# relais_node_01.net
KiCad netlist of a schematic drawn in EAGLE
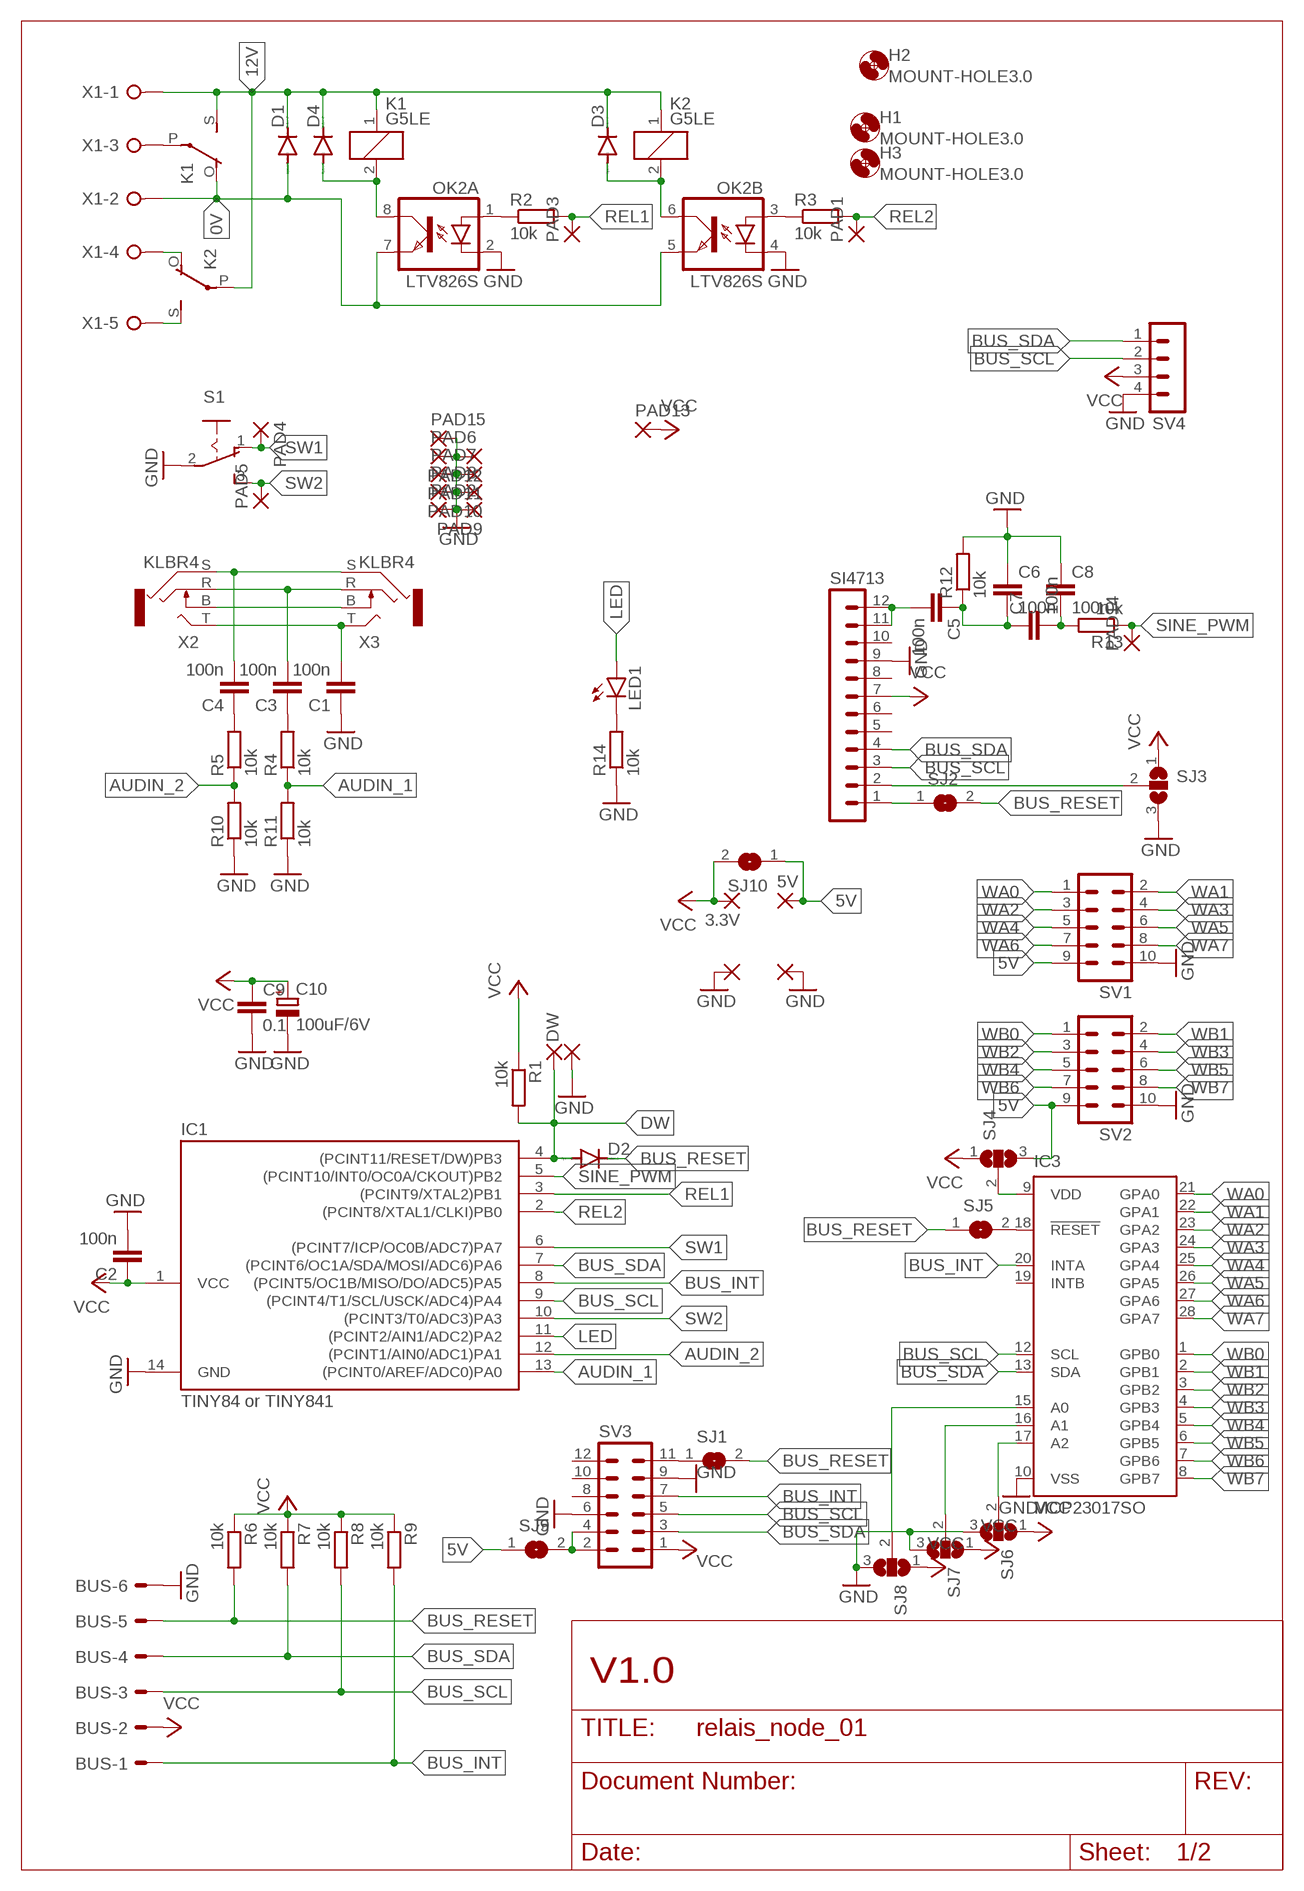
[diagram p0: schematic, sheet 1]

(export (version "E")
  (design (tool "Eeschema 10.0.6"))
  (components
    (comp (ref "3.3V")
      (value "1,6/0,8")
      (footprint "eagle-import:1,6_0,8")
      (libsource (lib "eagle-import") (part "1,6/0,8"))
    )
    (comp (ref "5V")
      (value "1,6/0,8")
      (footprint "eagle-import:1,6_0,8")
      (libsource (lib "eagle-import") (part "1,6/0,8"))
    )
    (comp (ref "BUS")
      (value "ML6LE")
      (footprint "eagle-import:ML6L")
      (libsource (lib "eagle-import") (part "ML6?EL"))
    )
    (comp (ref "C1")
      (value "100n")
      (footprint "eagle-import:C0805")
      (libsource (lib "eagle-import") (part "C-EUC0805"))
    )
    (comp (ref "C2")
      (value "100n")
      (footprint "eagle-import:C0805")
      (libsource (lib "eagle-import") (part "C-EUC0805"))
    )
    (comp (ref "C3")
      (value "100n")
      (footprint "eagle-import:C0805")
      (libsource (lib "eagle-import") (part "C-EUC0805"))
    )
    (comp (ref "C4")
      (value "100n")
      (footprint "eagle-import:C0805")
      (libsource (lib "eagle-import") (part "C-EUC0805"))
    )
    (comp (ref "C5")
      (value "100n")
      (footprint "eagle-import:C0805")
      (libsource (lib "eagle-import") (part "C-EUC0805"))
    )
    (comp (ref "C6")
      (value "100n")
      (footprint "eagle-import:C0805")
      (libsource (lib "eagle-import") (part "C-EUC0805"))
    )
    (comp (ref "C7")
      (value "100n")
      (footprint "eagle-import:C0805")
      (libsource (lib "eagle-import") (part "C-EUC0805"))
    )
    (comp (ref "C8")
      (value "100n")
      (footprint "eagle-import:C0805")
      (libsource (lib "eagle-import") (part "C-EUC0805"))
    )
    (comp (ref "C9")
      (value "0.1")
      (footprint "eagle-import:C0805")
      (libsource (lib "eagle-import") (part "C-EUC0805"))
    )
    (comp (ref "C10")
      (value "100uF/6V")
      (footprint "eagle-import:B_3528-21R")
      (libsource (lib "eagle-import") (part "CPOL-EUB/3528-21R"))
    )
    (comp (ref "D1")
      (value "DIODE-MELF-MLL41")
      (footprint "eagle-import:MELF-MLL41")
      (libsource (lib "eagle-import") (part "DIODE-MELF-MLL41"))
    )
    (comp (ref "D2")
      (value "DIODE-MINIMELF")
      (footprint "eagle-import:MINIMELF")
      (libsource (lib "eagle-import") (part "DIODE-MINIMELF"))
    )
    (comp (ref "D3")
      (value "DIODE-MINIMELF")
      (footprint "eagle-import:MINIMELF")
      (libsource (lib "eagle-import") (part "DIODE-MINIMELF"))
    )
    (comp (ref "D4")
      (value "DIODE-MINIMELF")
      (footprint "eagle-import:MINIMELF")
      (libsource (lib "eagle-import") (part "DIODE-MINIMELF"))
    )
    (comp (ref "DW")
      (value "1,6/0,9")
      (footprint "eagle-import:1,6_0,9")
      (libsource (lib "eagle-import") (part "1,6/0,9"))
    )
    (comp (ref "GND_")
      (value "1,6/0,9")
      (footprint "eagle-import:1,6_0,9")
      (libsource (lib "eagle-import") (part "1,6/0,9"))
    )
    (comp (ref "H1")
      (value "MOUNT-HOLE3.0")
      (footprint "eagle-import:3,0")
      (libsource (lib "eagle-import") (part "MOUNT-HOLE3.0"))
    )
    (comp (ref "H2")
      (value "MOUNT-HOLE3.0")
      (footprint "eagle-import:3,0")
      (libsource (lib "eagle-import") (part "MOUNT-HOLE3.0"))
    )
    (comp (ref "H3")
      (value "MOUNT-HOLE3.0")
      (footprint "eagle-import:3,0")
      (libsource (lib "eagle-import") (part "MOUNT-HOLE3.0"))
    )
    (comp (ref "IC1")
      (value "TINY84 or TINY841")
      (footprint "eagle-import:SOIC14")
      (libsource (lib "eagle-import") (part "TINY24/44/84-SSU"))
    )
    (comp (ref "IC3")
      (value "MCP23017SO")
      (footprint "eagle-import:SO28W")
      (libsource (lib "eagle-import") (part "MCP23017SO"))
    )
    (comp (ref "K1")
      (value "G5LE")
      (footprint "eagle-import:G5LE")
      (libsource (lib "eagle-import") (part "G5LE"))
    )
    (comp (ref "K2")
      (value "G5LE")
      (footprint "eagle-import:G5LE")
      (libsource (lib "eagle-import") (part "G5LE"))
    )
    (comp (ref "LED1")
      (value "LED3MM")
      (footprint "eagle-import:LED3MM")
      (libsource (lib "eagle-import") (part "LED3MM"))
    )
    (comp (ref "OK2")
      (value "LTV826S")
      (footprint "eagle-import:DIL8-SMD")
      (libsource (lib "eagle-import") (part "LTV826S"))
    )
    (comp (ref "PAD1")
      (value "1,6/0,8")
      (footprint "eagle-import:1,6_0,8")
      (libsource (lib "eagle-import") (part "1,6/0,8"))
    )
    (comp (ref "PAD2")
      (value "1,6/0,8")
      (footprint "eagle-import:1,6_0,8")
      (libsource (lib "eagle-import") (part "1,6/0,8"))
    )
    (comp (ref "PAD3")
      (value "1,6/0,8")
      (footprint "eagle-import:1,6_0,8")
      (libsource (lib "eagle-import") (part "1,6/0,8"))
    )
    (comp (ref "PAD4")
      (value "1,6/0,8")
      (footprint "eagle-import:1,6_0,8")
      (libsource (lib "eagle-import") (part "1,6/0,8"))
    )
    (comp (ref "PAD5")
      (value "1,6/0,8")
      (footprint "eagle-import:1,6_0,8")
      (libsource (lib "eagle-import") (part "1,6/0,8"))
    )
    (comp (ref "PAD6")
      (value "1,6/0,8")
      (footprint "eagle-import:1,6_0,8")
      (libsource (lib "eagle-import") (part "1,6/0,8"))
    )
    (comp (ref "PAD7")
      (value "1,6/0,8")
      (footprint "eagle-import:1,6_0,8")
      (libsource (lib "eagle-import") (part "1,6/0,8"))
    )
    (comp (ref "PAD8")
      (value "1,6/0,8")
      (footprint "eagle-import:1,6_0,8")
      (libsource (lib "eagle-import") (part "1,6/0,8"))
    )
    (comp (ref "PAD9")
      (value "1,6/0,8")
      (footprint "eagle-import:1,6_0,8")
      (libsource (lib "eagle-import") (part "1,6/0,8"))
    )
    (comp (ref "PAD10")
      (value "1,6/0,8")
      (footprint "eagle-import:1,6_0,8")
      (libsource (lib "eagle-import") (part "1,6/0,8"))
    )
    (comp (ref "PAD11")
      (value "1,6/0,8")
      (footprint "eagle-import:1,6_0,8")
      (libsource (lib "eagle-import") (part "1,6/0,8"))
    )
    (comp (ref "PAD12")
      (value "1,6/0,8")
      (footprint "eagle-import:1,6_0,8")
      (libsource (lib "eagle-import") (part "1,6/0,8"))
    )
    (comp (ref "PAD13")
      (value "1,6/0,8")
      (footprint "eagle-import:1,6_0,8")
      (libsource (lib "eagle-import") (part "1,6/0,8"))
    )
    (comp (ref "PAD14")
      (value "1,6/0,8")
      (footprint "eagle-import:1,6_0,8")
      (libsource (lib "eagle-import") (part "1,6/0,8"))
    )
    (comp (ref "PAD15")
      (value "1,6/0,8")
      (footprint "eagle-import:1,6_0,8")
      (libsource (lib "eagle-import") (part "1,6/0,8"))
    )
    (comp (ref "PAD16")
      (value "1,6/0,8")
      (footprint "eagle-import:1,6_0,8")
      (libsource (lib "eagle-import") (part "1,6/0,8"))
    )
    (comp (ref "PAD17")
      (value "1,6/0,8")
      (footprint "eagle-import:1,6_0,8")
      (libsource (lib "eagle-import") (part "1,6/0,8"))
    )
    (comp (ref "R1")
      (value "10k")
      (footprint "eagle-import:M0805")
      (libsource (lib "eagle-import") (part "R-EU_M0805"))
    )
    (comp (ref "R2")
      (value "10k")
      (footprint "eagle-import:M0805")
      (libsource (lib "eagle-import") (part "R-EU_M0805"))
    )
    (comp (ref "R3")
      (value "10k")
      (footprint "eagle-import:M0805")
      (libsource (lib "eagle-import") (part "R-EU_M0805"))
    )
    (comp (ref "R4")
      (value "10k")
      (footprint "eagle-import:M0805")
      (libsource (lib "eagle-import") (part "R-EU_M0805"))
    )
    (comp (ref "R5")
      (value "10k")
      (footprint "eagle-import:M0805")
      (libsource (lib "eagle-import") (part "R-EU_M0805"))
    )
    (comp (ref "R6")
      (value "10k")
      (footprint "eagle-import:M0805")
      (libsource (lib "eagle-import") (part "R-EU_M0805"))
    )
    (comp (ref "R7")
      (value "10k")
      (footprint "eagle-import:M0805")
      (libsource (lib "eagle-import") (part "R-EU_M0805"))
    )
    (comp (ref "R8")
      (value "10k")
      (footprint "eagle-import:M0805")
      (libsource (lib "eagle-import") (part "R-EU_M0805"))
    )
    (comp (ref "R9")
      (value "10k")
      (footprint "eagle-import:M0805")
      (libsource (lib "eagle-import") (part "R-EU_M0805"))
    )
    (comp (ref "R10")
      (value "10k")
      (footprint "eagle-import:M0805")
      (libsource (lib "eagle-import") (part "R-EU_M0805"))
    )
    (comp (ref "R11")
      (value "10k")
      (footprint "eagle-import:M0805")
      (libsource (lib "eagle-import") (part "R-EU_M0805"))
    )
    (comp (ref "R12")
      (value "10k")
      (footprint "eagle-import:M0805")
      (libsource (lib "eagle-import") (part "R-EU_M0805"))
    )
    (comp (ref "R13")
      (value "10k")
      (footprint "eagle-import:M0805")
      (libsource (lib "eagle-import") (part "R-EU_M0805"))
    )
    (comp (ref "R14")
      (value "10k")
      (footprint "eagle-import:M0805")
      (libsource (lib "eagle-import") (part "R-EU_M0805"))
    )
    (comp (ref "S1")
      (value "255SB")
      (footprint "eagle-import:255SB")
      (libsource (lib "eagle-import") (part "255SB"))
    )
    (comp (ref "SI4713")
      (value "MA12-1")
      (footprint "eagle-import:MA12-1")
      (libsource (lib "eagle-import") (part "MA12-1"))
    )
    (comp (ref "SJ1") (value "SJ") (footprint "eagle-import:SJ") (libsource (lib "eagle-import") (part "SJ")))
    (comp (ref "SJ2") (value "SJ") (footprint "eagle-import:SJ") (libsource (lib "eagle-import") (part "SJ")))
    (comp (ref "SJ3")
      (value "SJ2W")
      (footprint "eagle-import:SJ_2")
      (libsource (lib "eagle-import") (part "SJ2W"))
    )
    (comp (ref "SJ4")
      (value "SJ2W")
      (footprint "eagle-import:SJ_2")
      (libsource (lib "eagle-import") (part "SJ2W"))
    )
    (comp (ref "SJ5") (value "SJ") (footprint "eagle-import:SJ") (libsource (lib "eagle-import") (part "SJ")))
    (comp (ref "SJ6")
      (value "SJ2W")
      (footprint "eagle-import:SJ_2")
      (libsource (lib "eagle-import") (part "SJ2W"))
    )
    (comp (ref "SJ7")
      (value "SJ2W")
      (footprint "eagle-import:SJ_2")
      (libsource (lib "eagle-import") (part "SJ2W"))
    )
    (comp (ref "SJ8")
      (value "SJ2W")
      (footprint "eagle-import:SJ_2")
      (libsource (lib "eagle-import") (part "SJ2W"))
    )
    (comp (ref "SJ9") (value "SJ") (footprint "eagle-import:SJ") (libsource (lib "eagle-import") (part "SJ")))
    (comp (ref "SJ10")
      (value "SJ")
      (footprint "eagle-import:SJ")
      (libsource (lib "eagle-import") (part "SJ"))
    )
    (comp (ref "SV1")
      (value "ML10")
      (footprint "eagle-import:ML10")
      (libsource (lib "eagle-import") (part "ML10"))
    )
    (comp (ref "SV2")
      (value "ML10")
      (footprint "eagle-import:ML10")
      (libsource (lib "eagle-import") (part "ML10"))
    )
    (comp (ref "SV3")
      (value "MA06-2")
      (footprint "eagle-import:MA06-2")
      (libsource (lib "eagle-import") (part "MA06-2"))
    )
    (comp (ref "SV4")
      (value "MA04-1")
      (footprint "eagle-import:MA04-1")
      (libsource (lib "eagle-import") (part "MA04-1"))
    )
    (comp (ref "X1")
      (value "W237-05P")
      (footprint "eagle-import:W237-5P")
      (libsource (lib "eagle-import") (part "W237-05P"))
    )
    (comp (ref "X2")
      (value "KLBR4")
      (footprint "eagle-import:KLBR4")
      (fields (field (name "MPN") "KLBR 4"))
      (libsource (lib "eagle-import") (part "KLBR4"))
    )
    (comp (ref "X3")
      (value "KLBR4")
      (footprint "eagle-import:KLBR4")
      (fields (field (name "MPN") "KLBR 4"))
      (libsource (lib "eagle-import") (part "KLBR4"))
    )
  )
  (nets
    (net (code "1") (name "0V") (class "Default")
      (node (ref "D1") (pin "A") (pinfunction "A_A") (pintype "passive"))
      (node (ref "K1") (pin "O") (pinfunction "O_O") (pintype "passive"))
      (node (ref "OK2") (pin "5") (pinfunction "EMIT_5") (pintype "passive"))
      (node (ref "OK2") (pin "7") (pinfunction "EMIT_7") (pintype "passive"))
      (node (ref "X1") (pin "2") (pinfunction "KL_2") (pintype "passive"))
    )
    (net (code "2") (name "5V") (class "Default")
      (node (ref "5V") (pin "1") (pinfunction "P_1") (pintype "passive"))
      (node (ref "SJ10") (pin "1") (pinfunction "1_1") (pintype "passive"))
      (node (ref "SJ4") (pin "3") (pinfunction "3_3") (pintype "passive"))
      (node (ref "SJ9") (pin "1") (pinfunction "1_1") (pintype "passive"))
      (node (ref "SV1") (pin "9") (pinfunction "9_9") (pintype "passive"))
      (node (ref "SV2") (pin "9") (pinfunction "9_9") (pintype "passive"))
    )
    (net (code "3") (name "12V") (class "Default")
      (node (ref "D1") (pin "C") (pinfunction "C_C") (pintype "passive"))
      (node (ref "D3") (pin "C") (pinfunction "C_C") (pintype "passive"))
      (node (ref "D4") (pin "C") (pinfunction "C_C") (pintype "passive"))
      (node (ref "K1") (pin "1") (pinfunction "1_1") (pintype "passive"))
      (node (ref "K1") (pin "S") (pinfunction "S_S") (pintype "passive"))
      (node (ref "K2") (pin "1") (pinfunction "1_1") (pintype "passive"))
      (node (ref "K2") (pin "P") (pinfunction "P_P") (pintype "passive"))
      (node (ref "X1") (pin "1") (pinfunction "KL_1") (pintype "passive"))
    )
    (net (code "4") (name "AUDIN_1") (class "Default")
      (node (ref "IC1") (pin "13") (pinfunction "(PCINT0/AREF/ADC0)PA0_13") (pintype "bidirectional"))
      (node (ref "R11") (pin "2") (pinfunction "2_2") (pintype "passive"))
      (node (ref "R4") (pin "1") (pinfunction "1_1") (pintype "passive"))
    )
    (net (code "5") (name "AUDIN_2") (class "Default")
      (node (ref "IC1") (pin "12") (pinfunction "(PCINT1/AIN0/ADC1)PA1_12") (pintype "bidirectional"))
      (node (ref "R10") (pin "2") (pinfunction "2_2") (pintype "passive"))
      (node (ref "R5") (pin "1") (pinfunction "1_1") (pintype "passive"))
    )
    (net (code "6") (name "BUS_INT") (class "Default")
      (node (ref "BUS") (pin "1") (pinfunction "S_1") (pintype "passive"))
      (node (ref "IC1") (pin "8") (pinfunction "(PCINT5/OC1B/MISO/DO/ADC5)PA5_8") (pintype "bidirectional"))
      (node (ref "IC3") (pin "20") (pinfunction "INTA_20") (pintype "output"))
      (node (ref "R9") (pin "2") (pinfunction "2_2") (pintype "passive"))
      (node (ref "SV3") (pin "7") (pinfunction "7_7") (pintype "passive"))
    )
    (net (code "7") (name "BUS_RESET") (class "Default")
      (node (ref "BUS") (pin "5") (pinfunction "S_5") (pintype "passive"))
      (node (ref "D2") (pin "C") (pinfunction "C_C") (pintype "passive"))
      (node (ref "R6") (pin "2") (pinfunction "2_2") (pintype "passive"))
      (node (ref "SJ1") (pin "2") (pinfunction "2_2") (pintype "passive"))
      (node (ref "SJ2") (pin "2") (pinfunction "2_2") (pintype "passive"))
      (node (ref "SJ5") (pin "1") (pinfunction "1_1") (pintype "passive"))
    )
    (net (code "8") (name "BUS_SCL") (class "Default")
      (node (ref "BUS") (pin "3") (pinfunction "S_3") (pintype "passive"))
      (node (ref "IC1") (pin "9") (pinfunction "(PCINT4/T1/SCL/USCK/ADC4)PA4_9") (pintype "bidirectional"))
      (node (ref "IC3") (pin "12") (pinfunction "SCL_12") (pintype "input"))
      (node (ref "R8") (pin "2") (pinfunction "2_2") (pintype "passive"))
      (node (ref "SI4713") (pin "3") (pinfunction "3_3") (pintype "passive"))
      (node (ref "SV3") (pin "5") (pinfunction "5_5") (pintype "passive"))
      (node (ref "SV4") (pin "2") (pinfunction "2_2") (pintype "passive"))
    )
    (net (code "9") (name "BUS_SDA") (class "Default")
      (node (ref "BUS") (pin "4") (pinfunction "S_4") (pintype "passive"))
      (node (ref "IC1") (pin "7") (pinfunction "(PCINT6/OC1A/SDA/MOSI/ADC6)PA6_7") (pintype "bidirectional"))
      (node (ref "IC3") (pin "13") (pinfunction "SDA_13") (pintype "bidirectional"))
      (node (ref "R7") (pin "2") (pinfunction "2_2") (pintype "passive"))
      (node (ref "SI4713") (pin "4") (pinfunction "4_4") (pintype "passive"))
      (node (ref "SV3") (pin "3") (pinfunction "3_3") (pintype "passive"))
      (node (ref "SV4") (pin "1") (pinfunction "1_1") (pintype "passive"))
    )
    (net (code "10") (name "DW") (class "Default")
      (node (ref "D2") (pin "A") (pinfunction "A_A") (pintype "passive"))
      (node (ref "DW") (pin "1") (pinfunction "P_1") (pintype "passive"))
      (node (ref "IC1") (pin "4") (pinfunction "(PCINT11/RESET/DW)PB3_4") (pintype "bidirectional"))
      (node (ref "R1") (pin "2") (pinfunction "2_2") (pintype "passive"))
    )
    (net (code "11") (name "GND") (class "Default")
      (node (ref "BUS") (pin "6") (pinfunction "S_6") (pintype "passive"))
      (node (ref "C1") (pin "1") (pinfunction "1_1") (pintype "passive"))
      (node (ref "C10") (pin "-") (pinfunction "-_-") (pintype "passive"))
      (node (ref "C2") (pin "2") (pinfunction "2_2") (pintype "passive"))
      (node (ref "C6") (pin "1") (pinfunction "1_1") (pintype "passive"))
      (node (ref "C8") (pin "1") (pinfunction "1_1") (pintype "passive"))
      (node (ref "C9") (pin "2") (pinfunction "2_2") (pintype "passive"))
      (node (ref "GND_") (pin "1") (pinfunction "P_1") (pintype "passive"))
      (node (ref "IC1") (pin "14") (pinfunction "GND_14") (pintype "power_in"))
      (node (ref "IC3") (pin "10") (pinfunction "VSS_10") (pintype "power_in"))
      (node (ref "OK2") (pin "2") (pinfunction "C_2") (pintype "passive"))
      (node (ref "OK2") (pin "4") (pinfunction "C_4") (pintype "passive"))
      (node (ref "PAD10") (pin "1") (pinfunction "P_1") (pintype "passive"))
      (node (ref "PAD11") (pin "1") (pinfunction "P_1") (pintype "passive"))
      (node (ref "PAD12") (pin "1") (pinfunction "P_1") (pintype "passive"))
      (node (ref "PAD15") (pin "1") (pinfunction "P_1") (pintype "passive"))
      (node (ref "PAD16") (pin "1") (pinfunction "P_1") (pintype "passive"))
      (node (ref "PAD17") (pin "1") (pinfunction "P_1") (pintype "passive"))
      (node (ref "PAD2") (pin "1") (pinfunction "P_1") (pintype "passive"))
      (node (ref "PAD6") (pin "1") (pinfunction "P_1") (pintype "passive"))
      (node (ref "PAD7") (pin "1") (pinfunction "P_1") (pintype "passive"))
      (node (ref "PAD8") (pin "1") (pinfunction "P_1") (pintype "passive"))
      (node (ref "PAD9") (pin "1") (pinfunction "P_1") (pintype "passive"))
      (node (ref "R10") (pin "1") (pinfunction "1_1") (pintype "passive"))
      (node (ref "R11") (pin "1") (pinfunction "1_1") (pintype "passive"))
      (node (ref "R12") (pin "2") (pinfunction "2_2") (pintype "passive"))
      (node (ref "R14") (pin "1") (pinfunction "1_1") (pintype "passive"))
      (node (ref "S1") (pin "2") (pinfunction "P_2") (pintype "passive"))
      (node (ref "SI4713") (pin "9") (pinfunction "9_9") (pintype "passive"))
      (node (ref "SJ3") (pin "3") (pinfunction "3_3") (pintype "passive"))
      (node (ref "SJ6") (pin "3") (pinfunction "3_3") (pintype "passive"))
      (node (ref "SJ7") (pin "3") (pinfunction "3_3") (pintype "passive"))
      (node (ref "SJ8") (pin "3") (pinfunction "3_3") (pintype "passive"))
      (node (ref "SV1") (pin "10") (pinfunction "10_10") (pintype "passive"))
      (node (ref "SV2") (pin "10") (pinfunction "10_10") (pintype "passive"))
      (node (ref "SV3") (pin "6") (pinfunction "6_6") (pintype "passive"))
      (node (ref "SV3") (pin "9") (pinfunction "9_9") (pintype "passive"))
      (node (ref "SV4") (pin "4") (pinfunction "4_4") (pintype "passive"))
    )
    (net (code "12") (name "LED") (class "Default")
      (node (ref "IC1") (pin "11") (pinfunction "(PCINT2/AIN1/ADC2)PA2_11") (pintype "bidirectional"))
      (node (ref "LED1") (pin "A") (pinfunction "A_A") (pintype "passive"))
    )
    (net (code "13") (name "Net-(C1-Pad2)") (class "Default")
      (node (ref "C1") (pin "2") (pinfunction "2_2") (pintype "passive"))
      (node (ref "X2") (pin "T") (pinfunction "T_T") (pintype "passive"))
      (node (ref "X3") (pin "T") (pinfunction "T_T") (pintype "passive"))
    )
    (net (code "14") (name "Net-(C3-Pad1)") (class "Default")
      (node (ref "C3") (pin "1") (pinfunction "1_1") (pintype "passive"))
      (node (ref "R4") (pin "2") (pinfunction "2_2") (pintype "passive"))
    )
    (net (code "15") (name "Net-(C3-Pad2)") (class "Default")
      (node (ref "C3") (pin "2") (pinfunction "2_2") (pintype "passive"))
      (node (ref "X2") (pin "R") (pinfunction "R_R") (pintype "passive"))
      (node (ref "X3") (pin "R") (pinfunction "R_R") (pintype "passive"))
    )
    (net (code "16") (name "Net-(C4-Pad1)") (class "Default")
      (node (ref "C4") (pin "1") (pinfunction "1_1") (pintype "passive"))
      (node (ref "R5") (pin "2") (pinfunction "2_2") (pintype "passive"))
    )
    (net (code "17") (name "Net-(C4-Pad2)") (class "Default")
      (node (ref "C4") (pin "2") (pinfunction "2_2") (pintype "passive"))
      (node (ref "X2") (pin "S") (pinfunction "S_S") (pintype "passive"))
      (node (ref "X3") (pin "S") (pinfunction "S_S") (pintype "passive"))
    )
    (net (code "18") (name "Net-(C5-Pad1)") (class "Default")
      (node (ref "C5") (pin "1") (pinfunction "1_1") (pintype "passive"))
      (node (ref "C6") (pin "2") (pinfunction "2_2") (pintype "passive"))
      (node (ref "C7") (pin "1") (pinfunction "1_1") (pintype "passive"))
      (node (ref "R12") (pin "1") (pinfunction "1_1") (pintype "passive"))
    )
    (net (code "19") (name "Net-(C5-Pad2)") (class "Default")
      (node (ref "C5") (pin "2") (pinfunction "2_2") (pintype "passive"))
      (node (ref "SI4713") (pin "11") (pinfunction "11_11") (pintype "passive"))
      (node (ref "SI4713") (pin "12") (pinfunction "12_12") (pintype "passive"))
    )
    (net (code "20") (name "Net-(C7-Pad2)") (class "Default")
      (node (ref "C7") (pin "2") (pinfunction "2_2") (pintype "passive"))
      (node (ref "C8") (pin "2") (pinfunction "2_2") (pintype "passive"))
      (node (ref "R13") (pin "2") (pinfunction "2_2") (pintype "passive"))
    )
    (net (code "21") (name "Net-(IC3-A0)") (class "Default")
      (node (ref "IC3") (pin "15") (pinfunction "A0_15") (pintype "input"))
      (node (ref "SJ8") (pin "2") (pinfunction "2_2") (pintype "passive"))
    )
    (net (code "22") (name "Net-(IC3-A1)") (class "Default")
      (node (ref "IC3") (pin "16") (pinfunction "A1_16") (pintype "input"))
      (node (ref "SJ7") (pin "2") (pinfunction "2_2") (pintype "passive"))
    )
    (net (code "23") (name "Net-(IC3-A2)") (class "Default")
      (node (ref "IC3") (pin "17") (pinfunction "A2_17") (pintype "input"))
      (node (ref "SJ6") (pin "2") (pinfunction "2_2") (pintype "passive"))
    )
    (net (code "24") (name "Net-(IC3-VDD)") (class "Default")
      (node (ref "IC3") (pin "9") (pinfunction "VDD_9") (pintype "power_in"))
      (node (ref "SJ4") (pin "2") (pinfunction "2_2") (pintype "passive"))
    )
    (net (code "25") (name "Net-(IC3-~{RESET})") (class "Default")
      (node (ref "IC3") (pin "18") (pinfunction "~{RESET}_18") (pintype "input"))
      (node (ref "SJ5") (pin "2") (pinfunction "2_2") (pintype "passive"))
    )
    (net (code "26") (name "Net-(LED1-C)") (class "Default")
      (node (ref "LED1") (pin "K") (pinfunction "C_K") (pintype "passive"))
      (node (ref "R14") (pin "2") (pinfunction "2_2") (pintype "passive"))
    )
    (net (code "27") (name "Net-(OK2A-A)") (class "Default")
      (node (ref "OK2") (pin "1") (pinfunction "A_1") (pintype "passive"))
      (node (ref "R2") (pin "1") (pinfunction "1_1") (pintype "passive"))
    )
    (net (code "28") (name "Net-(OK2A-COL)") (class "Default")
      (node (ref "D4") (pin "A") (pinfunction "A_A") (pintype "passive"))
      (node (ref "K1") (pin "2") (pinfunction "2_2") (pintype "passive"))
      (node (ref "OK2") (pin "8") (pinfunction "COL_8") (pintype "passive"))
    )
    (net (code "29") (name "Net-(OK2B-A)") (class "Default")
      (node (ref "OK2") (pin "3") (pinfunction "A_3") (pintype "passive"))
      (node (ref "R3") (pin "1") (pinfunction "1_1") (pintype "passive"))
    )
    (net (code "30") (name "Net-(OK2B-COL)") (class "Default")
      (node (ref "D3") (pin "A") (pinfunction "A_A") (pintype "passive"))
      (node (ref "K2") (pin "2") (pinfunction "2_2") (pintype "passive"))
      (node (ref "OK2") (pin "6") (pinfunction "COL_6") (pintype "passive"))
    )
    (net (code "31") (name "Net-(SI4713-Pad1)") (class "Default")
      (node (ref "SI4713") (pin "1") (pinfunction "1_1") (pintype "passive"))
      (node (ref "SJ2") (pin "1") (pinfunction "1_1") (pintype "passive"))
    )
    (net (code "32") (name "Net-(SI4713-Pad2)") (class "Default")
      (node (ref "SI4713") (pin "2") (pinfunction "2_2") (pintype "passive"))
      (node (ref "SJ3") (pin "2") (pinfunction "2_2") (pintype "passive"))
    )
    (net (code "33") (name "Net-(SJ1-Pad1)") (class "Default")
      (node (ref "SJ1") (pin "1") (pinfunction "1_1") (pintype "passive"))
      (node (ref "SV3") (pin "11") (pinfunction "11_11") (pintype "passive"))
    )
    (net (code "34") (name "Net-(SJ9-Pad2)") (class "Default")
      (node (ref "SJ9") (pin "2") (pinfunction "2_2") (pintype "passive"))
      (node (ref "SV3") (pin "2") (pinfunction "2_2") (pintype "passive"))
      (node (ref "SV3") (pin "4") (pinfunction "4_4") (pintype "passive"))
    )
    (net (code "35") (name "Net-(X1C-KL)") (class "Default")
      (node (ref "K1") (pin "P") (pinfunction "P_P") (pintype "passive"))
      (node (ref "X1") (pin "3") (pinfunction "KL_3") (pintype "passive"))
    )
    (net (code "36") (name "Net-(X1D-KL)") (class "Default")
      (node (ref "K2") (pin "O") (pinfunction "O_O") (pintype "passive"))
      (node (ref "X1") (pin "4") (pinfunction "KL_4") (pintype "passive"))
    )
    (net (code "37") (name "Net-(X1E-KL)") (class "Default")
      (node (ref "K2") (pin "S") (pinfunction "S_S") (pintype "passive"))
      (node (ref "X1") (pin "5") (pinfunction "KL_5") (pintype "passive"))
    )
    (net (code "38") (name "Net-(X2-PadB)") (class "Default")
      (node (ref "X2") (pin "B") (pinfunction "B_B") (pintype "passive"))
      (node (ref "X3") (pin "B") (pinfunction "B_B") (pintype "passive"))
    )
    (net (code "39") (name "REL1") (class "Default")
      (node (ref "IC1") (pin "3") (pinfunction "(PCINT9/XTAL2)PB1_3") (pintype "bidirectional"))
      (node (ref "PAD3") (pin "1") (pinfunction "P_1") (pintype "passive"))
      (node (ref "R2") (pin "2") (pinfunction "2_2") (pintype "passive"))
    )
    (net (code "40") (name "REL2") (class "Default")
      (node (ref "IC1") (pin "2") (pinfunction "(PCINT8/XTAL1/CLKI)PB0_2") (pintype "bidirectional"))
      (node (ref "PAD1") (pin "1") (pinfunction "P_1") (pintype "passive"))
      (node (ref "R3") (pin "2") (pinfunction "2_2") (pintype "passive"))
    )
    (net (code "41") (name "SINE_PWM") (class "Default")
      (node (ref "IC1") (pin "5") (pinfunction "(PCINT10/INT0/OC0A/CKOUT)PB2_5") (pintype "bidirectional"))
      (node (ref "PAD14") (pin "1") (pinfunction "P_1") (pintype "passive"))
      (node (ref "R13") (pin "1") (pinfunction "1_1") (pintype "passive"))
    )
    (net (code "42") (name "SW1") (class "Default")
      (node (ref "IC1") (pin "6") (pinfunction "(PCINT7/ICP/OC0B/ADC7)PA7_6") (pintype "bidirectional"))
      (node (ref "PAD4") (pin "1") (pinfunction "P_1") (pintype "passive"))
      (node (ref "S1") (pin "1") (pinfunction "O_1") (pintype "passive"))
    )
    (net (code "43") (name "SW2") (class "Default")
      (node (ref "IC1") (pin "10") (pinfunction "(PCINT3/T0/ADC3)PA3_10") (pintype "bidirectional"))
      (node (ref "PAD5") (pin "1") (pinfunction "P_1") (pintype "passive"))
      (node (ref "S1") (pin "3") (pinfunction "S_3") (pintype "passive"))
    )
    (net (code "44") (name "VCC") (class "Default")
      (node (ref "3.3V") (pin "1") (pinfunction "P_1") (pintype "passive"))
      (node (ref "BUS") (pin "2") (pinfunction "S_2") (pintype "passive"))
      (node (ref "C10") (pin "+") (pinfunction "+_+") (pintype "passive"))
      (node (ref "C2") (pin "1") (pinfunction "1_1") (pintype "passive"))
      (node (ref "C9") (pin "1") (pinfunction "1_1") (pintype "passive"))
      (node (ref "IC1") (pin "1") (pinfunction "VCC_1") (pintype "power_in"))
      (node (ref "PAD13") (pin "1") (pinfunction "P_1") (pintype "passive"))
      (node (ref "R1") (pin "1") (pinfunction "1_1") (pintype "passive"))
      (node (ref "R6") (pin "1") (pinfunction "1_1") (pintype "passive"))
      (node (ref "R7") (pin "1") (pinfunction "1_1") (pintype "passive"))
      (node (ref "R8") (pin "1") (pinfunction "1_1") (pintype "passive"))
      (node (ref "R9") (pin "1") (pinfunction "1_1") (pintype "passive"))
      (node (ref "SI4713") (pin "7") (pinfunction "7_7") (pintype "passive"))
      (node (ref "SJ10") (pin "2") (pinfunction "2_2") (pintype "passive"))
      (node (ref "SJ3") (pin "1") (pinfunction "1_1") (pintype "passive"))
      (node (ref "SJ4") (pin "1") (pinfunction "1_1") (pintype "passive"))
      (node (ref "SJ6") (pin "1") (pinfunction "1_1") (pintype "passive"))
      (node (ref "SJ7") (pin "1") (pinfunction "1_1") (pintype "passive"))
      (node (ref "SJ8") (pin "1") (pinfunction "1_1") (pintype "passive"))
      (node (ref "SV3") (pin "1") (pinfunction "1_1") (pintype "passive"))
      (node (ref "SV4") (pin "3") (pinfunction "3_3") (pintype "passive"))
    )
    (net (code "45") (name "WA0") (class "Default")
      (node (ref "IC3") (pin "21") (pinfunction "GPA0_21") (pintype "bidirectional"))
      (node (ref "SV1") (pin "1") (pinfunction "1_1") (pintype "passive"))
    )
    (net (code "46") (name "WA1") (class "Default")
      (node (ref "IC3") (pin "22") (pinfunction "GPA1_22") (pintype "bidirectional"))
      (node (ref "SV1") (pin "2") (pinfunction "2_2") (pintype "passive"))
    )
    (net (code "47") (name "WA2") (class "Default")
      (node (ref "IC3") (pin "23") (pinfunction "GPA2_23") (pintype "bidirectional"))
      (node (ref "SV1") (pin "3") (pinfunction "3_3") (pintype "passive"))
    )
    (net (code "48") (name "WA3") (class "Default")
      (node (ref "IC3") (pin "24") (pinfunction "GPA3_24") (pintype "bidirectional"))
      (node (ref "SV1") (pin "4") (pinfunction "4_4") (pintype "passive"))
    )
    (net (code "49") (name "WA4") (class "Default")
      (node (ref "IC3") (pin "25") (pinfunction "GPA4_25") (pintype "bidirectional"))
      (node (ref "SV1") (pin "5") (pinfunction "5_5") (pintype "passive"))
    )
    (net (code "50") (name "WA5") (class "Default")
      (node (ref "IC3") (pin "26") (pinfunction "GPA5_26") (pintype "bidirectional"))
      (node (ref "SV1") (pin "6") (pinfunction "6_6") (pintype "passive"))
    )
    (net (code "51") (name "WA6") (class "Default")
      (node (ref "IC3") (pin "27") (pinfunction "GPA6_27") (pintype "bidirectional"))
      (node (ref "SV1") (pin "7") (pinfunction "7_7") (pintype "passive"))
    )
    (net (code "52") (name "WA7") (class "Default")
      (node (ref "IC3") (pin "28") (pinfunction "GPA7_28") (pintype "bidirectional"))
      (node (ref "SV1") (pin "8") (pinfunction "8_8") (pintype "passive"))
    )
    (net (code "53") (name "WB0") (class "Default")
      (node (ref "IC3") (pin "1") (pinfunction "GPB0_1") (pintype "bidirectional"))
      (node (ref "SV2") (pin "1") (pinfunction "1_1") (pintype "passive"))
    )
    (net (code "54") (name "WB1") (class "Default")
      (node (ref "IC3") (pin "2") (pinfunction "GPB1_2") (pintype "bidirectional"))
      (node (ref "SV2") (pin "2") (pinfunction "2_2") (pintype "passive"))
    )
    (net (code "55") (name "WB2") (class "Default")
      (node (ref "IC3") (pin "3") (pinfunction "GPB2_3") (pintype "bidirectional"))
      (node (ref "SV2") (pin "3") (pinfunction "3_3") (pintype "passive"))
    )
    (net (code "56") (name "WB3") (class "Default")
      (node (ref "IC3") (pin "4") (pinfunction "GPB3_4") (pintype "bidirectional"))
      (node (ref "SV2") (pin "4") (pinfunction "4_4") (pintype "passive"))
    )
    (net (code "57") (name "WB4") (class "Default")
      (node (ref "IC3") (pin "5") (pinfunction "GPB4_5") (pintype "bidirectional"))
      (node (ref "SV2") (pin "5") (pinfunction "5_5") (pintype "passive"))
    )
    (net (code "58") (name "WB5") (class "Default")
      (node (ref "IC3") (pin "6") (pinfunction "GPB5_6") (pintype "bidirectional"))
      (node (ref "SV2") (pin "6") (pinfunction "6_6") (pintype "passive"))
    )
    (net (code "59") (name "WB6") (class "Default")
      (node (ref "IC3") (pin "7") (pinfunction "GPB6_7") (pintype "bidirectional"))
      (node (ref "SV2") (pin "7") (pinfunction "7_7") (pintype "passive"))
    )
    (net (code "60") (name "WB7") (class "Default")
      (node (ref "IC3") (pin "8") (pinfunction "GPB7_8") (pintype "bidirectional"))
      (node (ref "SV2") (pin "8") (pinfunction "8_8") (pintype "passive"))
    )
    (net (code "61") (name "unconnected-(IC3-INTB-Pad19)") (class "Default")
      (node (ref "IC3") (pin "19") (pinfunction "INTB_19") (pintype "output"))
    )
    (net (code "62") (name "unconnected-(SI4713-Pad5)") (class "Default")
      (node (ref "SI4713") (pin "5") (pinfunction "5_5") (pintype "passive"))
    )
    (net (code "63") (name "unconnected-(SI4713-Pad6)") (class "Default")
      (node (ref "SI4713") (pin "6") (pinfunction "6_6") (pintype "passive"))
    )
    (net (code "64") (name "unconnected-(SI4713-Pad8)") (class "Default")
      (node (ref "SI4713") (pin "8") (pinfunction "8_8") (pintype "passive"))
    )
    (net (code "65") (name "unconnected-(SI4713-Pad10)") (class "Default")
      (node (ref "SI4713") (pin "10") (pinfunction "10_10") (pintype "passive"))
    )
    (net (code "66") (name "unconnected-(SV3-Pad8)") (class "Default")
      (node (ref "SV3") (pin "8") (pinfunction "8_8") (pintype "passive"))
    )
    (net (code "67") (name "unconnected-(SV3-Pad10)") (class "Default")
      (node (ref "SV3") (pin "10") (pinfunction "10_10") (pintype "passive"))
    )
    (net (code "68") (name "unconnected-(SV3-Pad12)") (class "Default")
      (node (ref "SV3") (pin "12") (pinfunction "12_12") (pintype "passive"))
    )
  )
)
